# BoardConnectors.net
KiCad netlist of a schematic drawn in Altium Designer
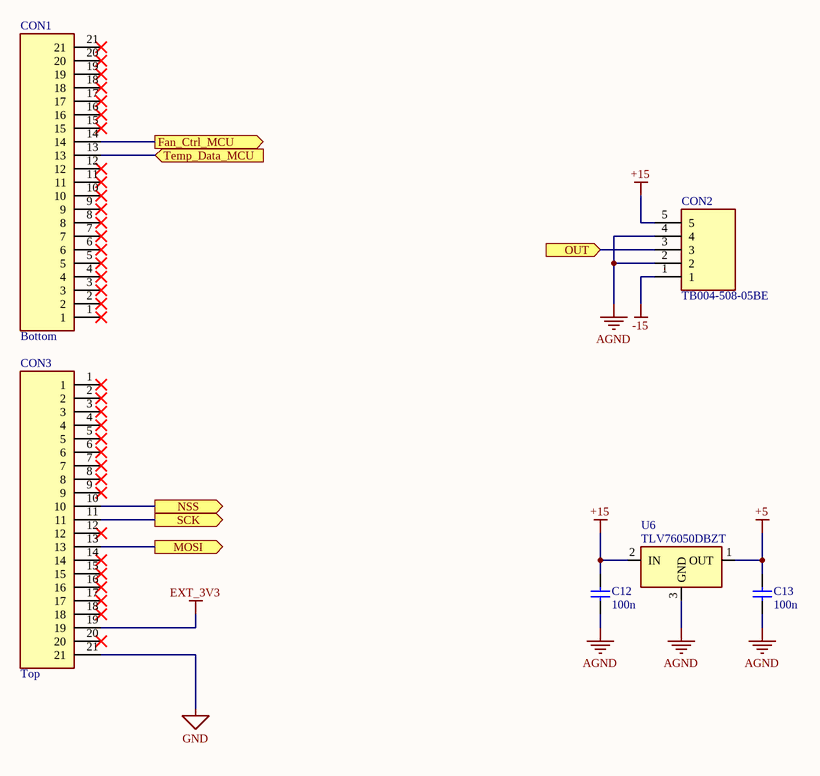
[diagram p0: BoardConnectors.SchDoc]

(export (version "E")
  (design (tool "Eeschema 10.0.6"))
  (components
    (comp (ref "C12")
      (value "100n")
      (footprint "Cap_0603_MD_outline")
      (description "Capacitor")
      (fields (field (name "MPN") "GRM188R72A104KA35"))
      (libsource (lib "LibPassive") (part "Capacitor"))
    )
    (comp (ref "C13")
      (value "100n")
      (footprint "Cap_0603_MD_outline")
      (description "Capacitor")
      (fields (field (name "MPN") "GRM188R72A104KA35"))
      (libsource (lib "LibPassive") (part "Capacitor"))
    )
    (comp (ref "CON1")
      (value "Socket 21")
      (footprint "SOCKET_1X21_2.54")
      (description "Socket, 21-Pin")
      (fields (field (name "LOCATION") "Bottom"))
      (libsource (lib "") (part "Socket 21_1"))
    )
    (comp (ref "CON2")
      (value "TB004-508-05BE")
      (footprint "TB00450805BE")
      (description "Terminal Block Screw")
      (libsource (lib "Library") (part "TB004-508-05BE"))
    )
    (comp (ref "CON3")
      (value "Socket 21")
      (footprint "SOCKET_1X21_2.54")
      (description "Socket, 21-Pin")
      (fields (field (name "LOCATION") "Top"))
      (libsource (lib "Library") (part "Socket 21"))
    )
    (comp (ref "U6")
      (value "TLV76050DBZT")
      (footprint "SOT95P237X112-3N")
      (description "Voltage Regulator 5V")
      (libsource (lib "Schlib") (part "TLV76050DBZT"))
    )
  )
  (nets
    (net (code "1") (name "+5") (class "Default")
      (node (ref "C13") (pin "2") (pinfunction "2_2") (pintype "passive"))
      (node (ref "U6") (pin "1") (pinfunction "OUT_1") (pintype "power_in"))
    )
    (net (code "2") (name "+15") (class "Default")
      (node (ref "C12") (pin "2") (pinfunction "2_2") (pintype "passive"))
      (node (ref "CON2") (pin "5") (pinfunction "5_5") (pintype "passive"))
      (node (ref "U6") (pin "2") (pinfunction "IN_2") (pintype "power_in"))
    )
    (net (code "3") (name "-15") (class "Default")
      (node (ref "CON2") (pin "1") (pinfunction "1_1") (pintype "passive"))
    )
    (net (code "4") (name "/Fan_Ctrl_MCU") (class "Default")
      (node (ref "CON1") (pin "14") (pinfunction "14_14") (pintype "passive"))
    )
    (net (code "5") (name "/MOSI") (class "Default")
      (node (ref "CON3") (pin "13") (pinfunction "13_13") (pintype "passive"))
    )
    (net (code "6") (name "/NSS") (class "Default")
      (node (ref "CON3") (pin "10") (pinfunction "10_10") (pintype "passive"))
    )
    (net (code "7") (name "/OUT") (class "Default")
      (node (ref "CON2") (pin "3") (pinfunction "3_3") (pintype "passive"))
    )
    (net (code "8") (name "/SCK") (class "Default")
      (node (ref "CON3") (pin "11") (pinfunction "11_11") (pintype "passive"))
    )
    (net (code "9") (name "/Temp_Data_MCU") (class "Default")
      (node (ref "CON1") (pin "13") (pinfunction "13_13") (pintype "passive"))
    )
    (net (code "10") (name "AGND") (class "Default")
      (node (ref "C12") (pin "1") (pinfunction "1_1") (pintype "passive"))
      (node (ref "C13") (pin "1") (pinfunction "1_1") (pintype "passive"))
      (node (ref "CON2") (pin "2") (pinfunction "2_2") (pintype "passive"))
      (node (ref "CON2") (pin "4") (pinfunction "4_4") (pintype "passive"))
      (node (ref "U6") (pin "3") (pinfunction "GND_3") (pintype "power_in"))
    )
    (net (code "11") (name "EXT_3V3") (class "Default")
      (node (ref "CON3") (pin "19") (pinfunction "19_19") (pintype "passive"))
    )
    (net (code "12") (name "GND") (class "Default")
      (node (ref "CON3") (pin "21") (pinfunction "21_21") (pintype "passive"))
    )
    (net (code "13") (name "unconnected-(CON1-Pad1)") (class "Default")
      (node (ref "CON1") (pin "1") (pinfunction "1_1") (pintype "passive+no_connect"))
    )
    (net (code "14") (name "unconnected-(CON1-Pad2)") (class "Default")
      (node (ref "CON1") (pin "2") (pinfunction "2_2") (pintype "passive+no_connect"))
    )
    (net (code "15") (name "unconnected-(CON1-Pad3)") (class "Default")
      (node (ref "CON1") (pin "3") (pinfunction "3_3") (pintype "passive+no_connect"))
    )
    (net (code "16") (name "unconnected-(CON1-Pad4)") (class "Default")
      (node (ref "CON1") (pin "4") (pinfunction "4_4") (pintype "passive+no_connect"))
    )
    (net (code "17") (name "unconnected-(CON1-Pad5)") (class "Default")
      (node (ref "CON1") (pin "5") (pinfunction "5_5") (pintype "passive+no_connect"))
    )
    (net (code "18") (name "unconnected-(CON1-Pad6)") (class "Default")
      (node (ref "CON1") (pin "6") (pinfunction "6_6") (pintype "passive+no_connect"))
    )
    (net (code "19") (name "unconnected-(CON1-Pad7)") (class "Default")
      (node (ref "CON1") (pin "7") (pinfunction "7_7") (pintype "passive+no_connect"))
    )
    (net (code "20") (name "unconnected-(CON1-Pad8)") (class "Default")
      (node (ref "CON1") (pin "8") (pinfunction "8_8") (pintype "passive+no_connect"))
    )
    (net (code "21") (name "unconnected-(CON1-Pad9)") (class "Default")
      (node (ref "CON1") (pin "9") (pinfunction "9_9") (pintype "passive+no_connect"))
    )
    (net (code "22") (name "unconnected-(CON1-Pad10)") (class "Default")
      (node (ref "CON1") (pin "10") (pinfunction "10_10") (pintype "passive+no_connect"))
    )
    (net (code "23") (name "unconnected-(CON1-Pad11)") (class "Default")
      (node (ref "CON1") (pin "11") (pinfunction "11_11") (pintype "passive+no_connect"))
    )
    (net (code "24") (name "unconnected-(CON1-Pad12)") (class "Default")
      (node (ref "CON1") (pin "12") (pinfunction "12_12") (pintype "passive+no_connect"))
    )
    (net (code "25") (name "unconnected-(CON1-Pad15)") (class "Default")
      (node (ref "CON1") (pin "15") (pinfunction "15_15") (pintype "passive+no_connect"))
    )
    (net (code "26") (name "unconnected-(CON1-Pad16)") (class "Default")
      (node (ref "CON1") (pin "16") (pinfunction "16_16") (pintype "passive+no_connect"))
    )
    (net (code "27") (name "unconnected-(CON1-Pad17)") (class "Default")
      (node (ref "CON1") (pin "17") (pinfunction "17_17") (pintype "passive+no_connect"))
    )
    (net (code "28") (name "unconnected-(CON1-Pad18)") (class "Default")
      (node (ref "CON1") (pin "18") (pinfunction "18_18") (pintype "passive+no_connect"))
    )
    (net (code "29") (name "unconnected-(CON1-Pad19)") (class "Default")
      (node (ref "CON1") (pin "19") (pinfunction "19_19") (pintype "passive+no_connect"))
    )
    (net (code "30") (name "unconnected-(CON1-Pad20)") (class "Default")
      (node (ref "CON1") (pin "20") (pinfunction "20_20") (pintype "passive+no_connect"))
    )
    (net (code "31") (name "unconnected-(CON1-Pad21)") (class "Default")
      (node (ref "CON1") (pin "21") (pinfunction "21_21") (pintype "passive+no_connect"))
    )
    (net (code "32") (name "unconnected-(CON3-Pad1)") (class "Default")
      (node (ref "CON3") (pin "1") (pinfunction "1_1") (pintype "passive+no_connect"))
    )
    (net (code "33") (name "unconnected-(CON3-Pad2)") (class "Default")
      (node (ref "CON3") (pin "2") (pinfunction "2_2") (pintype "passive+no_connect"))
    )
    (net (code "34") (name "unconnected-(CON3-Pad3)") (class "Default")
      (node (ref "CON3") (pin "3") (pinfunction "3_3") (pintype "passive+no_connect"))
    )
    (net (code "35") (name "unconnected-(CON3-Pad4)") (class "Default")
      (node (ref "CON3") (pin "4") (pinfunction "4_4") (pintype "passive+no_connect"))
    )
    (net (code "36") (name "unconnected-(CON3-Pad5)") (class "Default")
      (node (ref "CON3") (pin "5") (pinfunction "5_5") (pintype "passive+no_connect"))
    )
    (net (code "37") (name "unconnected-(CON3-Pad6)") (class "Default")
      (node (ref "CON3") (pin "6") (pinfunction "6_6") (pintype "passive+no_connect"))
    )
    (net (code "38") (name "unconnected-(CON3-Pad7)") (class "Default")
      (node (ref "CON3") (pin "7") (pinfunction "7_7") (pintype "passive+no_connect"))
    )
    (net (code "39") (name "unconnected-(CON3-Pad8)") (class "Default")
      (node (ref "CON3") (pin "8") (pinfunction "8_8") (pintype "passive+no_connect"))
    )
    (net (code "40") (name "unconnected-(CON3-Pad9)") (class "Default")
      (node (ref "CON3") (pin "9") (pinfunction "9_9") (pintype "passive+no_connect"))
    )
    (net (code "41") (name "unconnected-(CON3-Pad12)") (class "Default")
      (node (ref "CON3") (pin "12") (pinfunction "12_12") (pintype "passive+no_connect"))
    )
    (net (code "42") (name "unconnected-(CON3-Pad14)") (class "Default")
      (node (ref "CON3") (pin "14") (pinfunction "14_14") (pintype "passive+no_connect"))
    )
    (net (code "43") (name "unconnected-(CON3-Pad15)") (class "Default")
      (node (ref "CON3") (pin "15") (pinfunction "15_15") (pintype "passive+no_connect"))
    )
    (net (code "44") (name "unconnected-(CON3-Pad16)") (class "Default")
      (node (ref "CON3") (pin "16") (pinfunction "16_16") (pintype "passive+no_connect"))
    )
    (net (code "45") (name "unconnected-(CON3-Pad17)") (class "Default")
      (node (ref "CON3") (pin "17") (pinfunction "17_17") (pintype "passive+no_connect"))
    )
    (net (code "46") (name "unconnected-(CON3-Pad18)") (class "Default")
      (node (ref "CON3") (pin "18") (pinfunction "18_18") (pintype "passive+no_connect"))
    )
    (net (code "47") (name "unconnected-(CON3-Pad20)") (class "Default")
      (node (ref "CON3") (pin "20") (pinfunction "20_20") (pintype "passive+no_connect"))
    )
  )
)
